# Snap2_audio.net
KiCad netlist of a schematic drawn in Altium Designer
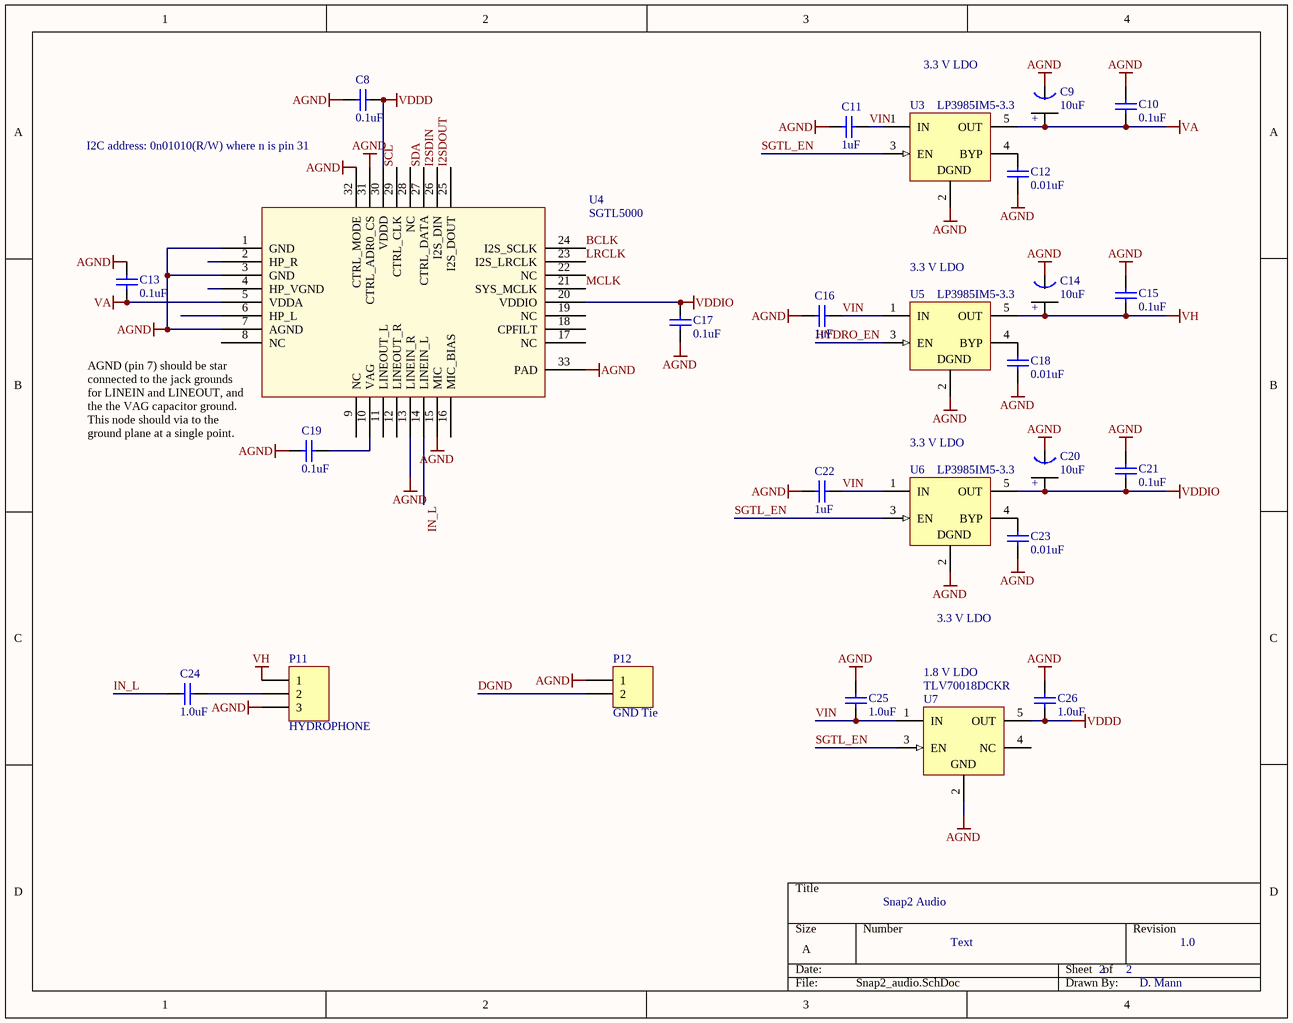
[diagram p0: Snap2_audio.SchDoc]

(export (version "E")
  (design (tool "Eeschema 10.0.6"))
  (components
    (comp (ref "C8")
      (value "0.1uF")
      (footprint "0402")
      (description "Ceramic Chip Capacitor - Standard")
      (fields (field (name "PUBLISHER") "Altium Limited"))
      (libsource (lib "KEMET Chip Capacitor") (part "C0402"))
    )
    (comp (ref "C9") (value "10uF") (footprint "Tant0805") (libsource (lib "Loggerhead") (part "Tant0805")))
    (comp (ref "C10")
      (value "0.1uF")
      (footprint "0402")
      (description "Ceramic Chip Capacitor - Standard")
      (fields (field (name "PUBLISHER") "Altium Limited"))
      (libsource (lib "KEMET Chip Capacitor") (part "C0402"))
    )
    (comp (ref "C11")
      (value "1uF")
      (footprint "0402")
      (description "Ceramic Chip Capacitor - Standard")
      (fields (field (name "PUBLISHER") "Altium Limited"))
      (libsource (lib "KEMET Chip Capacitor") (part "C0402"))
    )
    (comp (ref "C12")
      (value "0.01uF")
      (footprint "0402")
      (description "Ceramic Chip Capacitor - Standard")
      (fields (field (name "PUBLISHER") "Altium Limited"))
      (libsource (lib "KEMET Chip Capacitor") (part "C0402"))
    )
    (comp (ref "C13")
      (value "0.1uF")
      (footprint "0402")
      (description "Ceramic Chip Capacitor - Standard")
      (fields (field (name "PUBLISHER") "Altium Limited"))
      (libsource (lib "KEMET Chip Capacitor") (part "C0402"))
    )
    (comp (ref "C14") (value "10uF") (footprint "Tant0805") (libsource (lib "Loggerhead") (part "Tant0805")))
    (comp (ref "C15")
      (value "0.1uF")
      (footprint "0402")
      (description "Ceramic Chip Capacitor - Standard")
      (fields (field (name "PUBLISHER") "Altium Limited"))
      (libsource (lib "KEMET Chip Capacitor") (part "C0402"))
    )
    (comp (ref "C16")
      (value "1uF")
      (footprint "0402")
      (description "Ceramic Chip Capacitor - Standard")
      (fields (field (name "PUBLISHER") "Altium Limited"))
      (libsource (lib "KEMET Chip Capacitor") (part "C0402"))
    )
    (comp (ref "C17")
      (value "0.1uF")
      (footprint "0402")
      (description "Ceramic Chip Capacitor - Standard")
      (fields (field (name "PUBLISHER") "Altium Limited"))
      (libsource (lib "KEMET Chip Capacitor") (part "C0402"))
    )
    (comp (ref "C18")
      (value "0.01uF")
      (footprint "0402")
      (description "Ceramic Chip Capacitor - Standard")
      (fields (field (name "PUBLISHER") "Altium Limited"))
      (libsource (lib "KEMET Chip Capacitor") (part "C0402"))
    )
    (comp (ref "C19")
      (value "0.1uF")
      (footprint "0402")
      (description "Ceramic Chip Capacitor - Standard")
      (fields (field (name "PUBLISHER") "Altium Limited"))
      (libsource (lib "KEMET Chip Capacitor") (part "C0402"))
    )
    (comp (ref "C20") (value "10uF") (footprint "Tant0805") (libsource (lib "Loggerhead") (part "Tant0805")))
    (comp (ref "C21")
      (value "0.1uF")
      (footprint "0402")
      (description "Ceramic Chip Capacitor - Standard")
      (fields (field (name "PUBLISHER") "Altium Limited"))
      (libsource (lib "KEMET Chip Capacitor") (part "C0402"))
    )
    (comp (ref "C22")
      (value "1uF")
      (footprint "0402")
      (description "Ceramic Chip Capacitor - Standard")
      (fields (field (name "PUBLISHER") "Altium Limited"))
      (libsource (lib "KEMET Chip Capacitor") (part "C0402"))
    )
    (comp (ref "C23")
      (value "0.01uF")
      (footprint "0402")
      (description "Ceramic Chip Capacitor - Standard")
      (fields (field (name "PUBLISHER") "Altium Limited"))
      (libsource (lib "KEMET Chip Capacitor") (part "C0402"))
    )
    (comp (ref "C24")
      (value "1.0uF")
      (footprint "0402")
      (description "Ceramic Chip Capacitor - Standard")
      (fields (field (name "PUBLISHER") "Altium Limited"))
      (libsource (lib "KEMET Chip Capacitor") (part "C0402"))
    )
    (comp (ref "C25")
      (value "1.0uF")
      (footprint "0402")
      (description "Ceramic Chip Capacitor - Standard")
      (fields (field (name "PUBLISHER") "Altium Limited"))
      (libsource (lib "KEMET Chip Capacitor") (part "C0402"))
    )
    (comp (ref "C26")
      (value "1.0uF")
      (footprint "0402")
      (description "Ceramic Chip Capacitor - Standard")
      (fields (field (name "PUBLISHER") "Altium Limited"))
      (libsource (lib "KEMET Chip Capacitor") (part "C0402"))
    )
    (comp (ref "P11")
      (value "HYDROPHONE")
      (footprint "HDR1X3")
      (description "Header, 3-Pin")
      (fields (field (name "PUBLISHER") "Altium Limited"))
      (libsource (lib "Miscellaneous Connectors") (part "Header 3"))
    )
    (comp (ref "P12")
      (value "GND Tie")
      (footprint "HDR1X2")
      (description "Header, 2-Pin")
      (fields (field (name "PUBLISHER") "Altium Limited"))
      (libsource (lib "Miscellaneous Connectors") (part "Header 2"))
    )
    (comp (ref "U3")
      (value "LP3985IM5-3.3")
      (footprint "MF05A_N")
      (description "Micropower, 150mA Low-Noise Ultra Low-Dropout CMOS Voltage Regulator")
      (fields
        (field (name "MANUFACTURER") "National Semiconductor")
        (field (name "DIGIKEYPARTNUMBER") "LP3985IM5-3.3CT-ND")
        (field (name "PUBLISHER") "Altium Limited")
      )
      (libsource (lib "NSC LDO") (part "LP3985IM5-3.3"))
    )
    (comp (ref "U4") (value "SGTL5000") (footprint "QFN32") (libsource (lib "Loggerhead") (part "SGTL5000")))
    (comp (ref "U5")
      (value "LP3985IM5-3.3")
      (footprint "MF05A_N")
      (description "Micropower, 150mA Low-Noise Ultra Low-Dropout CMOS Voltage Regulator")
      (fields
        (field (name "MANUFACTURER") "National Semiconductor")
        (field (name "DIGIKEYPARTNUMBER") "LP3985IM5-3.3CT-ND")
        (field (name "PUBLISHER") "Altium Limited")
      )
      (libsource (lib "NSC LDO") (part "LP3985IM5-3.3"))
    )
    (comp (ref "U6")
      (value "LP3985IM5-3.3")
      (footprint "MF05A_N")
      (description "Micropower, 150mA Low-Noise Ultra Low-Dropout CMOS Voltage Regulator")
      (fields
        (field (name "MANUFACTURER") "National Semiconductor")
        (field (name "DIGIKEYPARTNUMBER") "LP3985IM5-3.3CT-ND")
        (field (name "PUBLISHER") "Altium Limited")
      )
      (libsource (lib "NSC LDO") (part "LP3985IM5-3.3"))
    )
    (comp (ref "U7")
      (value "TLV70018DCKR")
      (footprint "TI-DCK5_V")
      (fields (field (name "MANUFACTURER") "Texas Instruments"))
      (libsource (lib "TI Power Management Linear Regulator Single Channel LDO (0-350mA)") (part "TLV70018DCKR"))
    )
  )
  (nets
    (net (code "1") (name "/BCLK") (class "Default")
      (node (ref "U4") (pin "24") (pinfunction "I2S_SCLK_24") (pintype "passive"))
    )
    (net (code "2") (name "/DGND") (class "Default")
      (node (ref "P12") (pin "2") (pinfunction "2_2") (pintype "passive"))
    )
    (net (code "3") (name "/HYDRO_EN") (class "Default")
      (node (ref "U5") (pin "3") (pinfunction "EN_3") (pintype "input"))
    )
    (net (code "4") (name "/I2SDIN") (class "Default")
      (node (ref "U4") (pin "26") (pinfunction "I2S_DIN_26") (pintype "passive"))
    )
    (net (code "5") (name "/I2SDOUT") (class "Default")
      (node (ref "U4") (pin "25") (pinfunction "I2S_DOUT_25") (pintype "passive"))
    )
    (net (code "6") (name "/IN_L") (class "Default")
      (node (ref "C24") (pin "2") (pinfunction "2_2") (pintype "passive"))
      (node (ref "U4") (pin "14") (pinfunction "LINEIN_L_14") (pintype "passive"))
    )
    (net (code "7") (name "/LRCLK") (class "Default")
      (node (ref "U4") (pin "23") (pinfunction "I2S_LRCLK_23") (pintype "passive"))
    )
    (net (code "8") (name "/MCLK") (class "Default")
      (node (ref "U4") (pin "21") (pinfunction "SYS_MCLK_21") (pintype "passive"))
    )
    (net (code "9") (name "/SCL") (class "Default")
      (node (ref "U4") (pin "29") (pinfunction "CTRL_CLK_29") (pintype "passive"))
    )
    (net (code "10") (name "/SDA") (class "Default")
      (node (ref "U4") (pin "27") (pinfunction "CTRL_DATA_27") (pintype "passive"))
    )
    (net (code "11") (name "/SGTL_EN") (class "Default")
      (node (ref "U3") (pin "3") (pinfunction "EN_3") (pintype "input"))
      (node (ref "U6") (pin "3") (pinfunction "EN_3") (pintype "input"))
      (node (ref "U7") (pin "3") (pinfunction "EN_3") (pintype "input"))
    )
    (net (code "12") (name "/VIN") (class "Default")
      (node (ref "C11") (pin "1") (pinfunction "1_1") (pintype "passive"))
      (node (ref "C16") (pin "1") (pinfunction "1_1") (pintype "passive"))
      (node (ref "C22") (pin "1") (pinfunction "1_1") (pintype "passive"))
      (node (ref "C25") (pin "1") (pinfunction "1_1") (pintype "passive"))
      (node (ref "U3") (pin "1") (pinfunction "IN_1") (pintype "power_in"))
      (node (ref "U5") (pin "1") (pinfunction "IN_1") (pintype "power_in"))
      (node (ref "U6") (pin "1") (pinfunction "IN_1") (pintype "power_in"))
      (node (ref "U7") (pin "1") (pinfunction "IN_1") (pintype "power_in"))
    )
    (net (code "13") (name "AGND") (class "Default")
      (node (ref "C10") (pin "2") (pinfunction "2_2") (pintype "passive"))
      (node (ref "C11") (pin "2") (pinfunction "2_2") (pintype "passive"))
      (node (ref "C12") (pin "2") (pinfunction "2_2") (pintype "passive"))
      (node (ref "C13") (pin "2") (pinfunction "2_2") (pintype "passive"))
      (node (ref "C14") (pin "1") (pinfunction "GND_1") (pintype "passive"))
      (node (ref "C15") (pin "2") (pinfunction "2_2") (pintype "passive"))
      (node (ref "C16") (pin "2") (pinfunction "2_2") (pintype "passive"))
      (node (ref "C17") (pin "2") (pinfunction "2_2") (pintype "passive"))
      (node (ref "C18") (pin "2") (pinfunction "2_2") (pintype "passive"))
      (node (ref "C19") (pin "2") (pinfunction "2_2") (pintype "passive"))
      (node (ref "C20") (pin "1") (pinfunction "GND_1") (pintype "passive"))
      (node (ref "C21") (pin "2") (pinfunction "2_2") (pintype "passive"))
      (node (ref "C22") (pin "2") (pinfunction "2_2") (pintype "passive"))
      (node (ref "C23") (pin "2") (pinfunction "2_2") (pintype "passive"))
      (node (ref "C25") (pin "2") (pinfunction "2_2") (pintype "passive"))
      (node (ref "C26") (pin "2") (pinfunction "2_2") (pintype "passive"))
      (node (ref "C8") (pin "2") (pinfunction "2_2") (pintype "passive"))
      (node (ref "C9") (pin "1") (pinfunction "GND_1") (pintype "passive"))
      (node (ref "P11") (pin "3") (pinfunction "3_3") (pintype "passive"))
      (node (ref "P12") (pin "1") (pinfunction "1_1") (pintype "passive"))
      (node (ref "U3") (pin "2") (pinfunction "GND_2") (pintype "power_in"))
      (node (ref "U4") (pin "1") (pinfunction "GND_1") (pintype "passive"))
      (node (ref "U4") (pin "13") (pinfunction "LINEIN_R_13") (pintype "passive"))
      (node (ref "U4") (pin "15") (pinfunction "MIC_15") (pintype "passive"))
      (node (ref "U4") (pin "3") (pinfunction "GND_3") (pintype "passive"))
      (node (ref "U4") (pin "31") (pinfunction "CTRL_ADR0_CS_31") (pintype "passive"))
      (node (ref "U4") (pin "32") (pinfunction "CTRL_MODE_32") (pintype "passive"))
      (node (ref "U4") (pin "33") (pinfunction "PAD_33") (pintype "passive"))
      (node (ref "U4") (pin "7") (pinfunction "AGND_7") (pintype "passive"))
      (node (ref "U5") (pin "2") (pinfunction "GND_2") (pintype "power_in"))
      (node (ref "U6") (pin "2") (pinfunction "GND_2") (pintype "power_in"))
      (node (ref "U7") (pin "2") (pinfunction "GND_2") (pintype "power_in"))
    )
    (net (code "14") (name "Net-(C24-Pad1)") (class "Default")
      (node (ref "C24") (pin "1") (pinfunction "1_1") (pintype "passive"))
      (node (ref "P11") (pin "2") (pinfunction "2_2") (pintype "passive"))
    )
    (net (code "15") (name "Net-(U3-BYP)") (class "Default")
      (node (ref "C12") (pin "1") (pinfunction "1_1") (pintype "passive"))
      (node (ref "U3") (pin "4") (pinfunction "BYP_4") (pintype "passive"))
    )
    (net (code "16") (name "Net-(U4-VAG)") (class "Default")
      (node (ref "C19") (pin "1") (pinfunction "1_1") (pintype "passive"))
      (node (ref "U4") (pin "10") (pinfunction "VAG_10") (pintype "passive"))
    )
    (net (code "17") (name "Net-(U5-BYP)") (class "Default")
      (node (ref "C18") (pin "1") (pinfunction "1_1") (pintype "passive"))
      (node (ref "U5") (pin "4") (pinfunction "BYP_4") (pintype "passive"))
    )
    (net (code "18") (name "Net-(U6-BYP)") (class "Default")
      (node (ref "C23") (pin "1") (pinfunction "1_1") (pintype "passive"))
      (node (ref "U6") (pin "4") (pinfunction "BYP_4") (pintype "passive"))
    )
    (net (code "19") (name "VA") (class "Default")
      (node (ref "C10") (pin "1") (pinfunction "1_1") (pintype "passive"))
      (node (ref "C13") (pin "1") (pinfunction "1_1") (pintype "passive"))
      (node (ref "C9") (pin "2") (pinfunction "+_2") (pintype "passive"))
      (node (ref "U3") (pin "5") (pinfunction "OUT_5") (pintype "power_in"))
      (node (ref "U4") (pin "5") (pinfunction "VDDA_5") (pintype "passive"))
    )
    (net (code "20") (name "VDDD") (class "Default")
      (node (ref "C26") (pin "1") (pinfunction "1_1") (pintype "passive"))
      (node (ref "C8") (pin "1") (pinfunction "1_1") (pintype "passive"))
      (node (ref "U4") (pin "30") (pinfunction "VDDD_30") (pintype "passive"))
      (node (ref "U7") (pin "5") (pinfunction "OUT_5") (pintype "power_in"))
    )
    (net (code "21") (name "VDDIO") (class "Default")
      (node (ref "C17") (pin "1") (pinfunction "1_1") (pintype "passive"))
      (node (ref "C20") (pin "2") (pinfunction "+_2") (pintype "passive"))
      (node (ref "C21") (pin "1") (pinfunction "1_1") (pintype "passive"))
      (node (ref "U4") (pin "20") (pinfunction "VDDIO_20") (pintype "passive"))
      (node (ref "U6") (pin "5") (pinfunction "OUT_5") (pintype "power_in"))
    )
    (net (code "22") (name "VH") (class "Default")
      (node (ref "C14") (pin "2") (pinfunction "+_2") (pintype "passive"))
      (node (ref "C15") (pin "1") (pinfunction "1_1") (pintype "passive"))
      (node (ref "P11") (pin "1") (pinfunction "1_1") (pintype "passive"))
      (node (ref "U5") (pin "5") (pinfunction "OUT_5") (pintype "power_in"))
    )
    (net (code "23") (name "unconnected-(U4-CPFILT-Pad18)") (class "Default")
      (node (ref "U4") (pin "18") (pinfunction "CPFILT_18") (pintype "passive"))
    )
    (net (code "24") (name "unconnected-(U4-HP_L-Pad6)") (class "Default")
      (node (ref "U4") (pin "6") (pinfunction "HP_L_6") (pintype "passive"))
    )
    (net (code "25") (name "unconnected-(U4-HP_R-Pad2)") (class "Default")
      (node (ref "U4") (pin "2") (pinfunction "HP_R_2") (pintype "passive"))
    )
    (net (code "26") (name "unconnected-(U4-HP_VGND-Pad4)") (class "Default")
      (node (ref "U4") (pin "4") (pinfunction "HP_VGND_4") (pintype "passive"))
    )
    (net (code "27") (name "unconnected-(U4-LINEOUT_L-Pad11)") (class "Default")
      (node (ref "U4") (pin "11") (pinfunction "LINEOUT_L_11") (pintype "passive"))
    )
    (net (code "28") (name "unconnected-(U4-LINEOUT_R-Pad12)") (class "Default")
      (node (ref "U4") (pin "12") (pinfunction "LINEOUT_R_12") (pintype "passive"))
    )
    (net (code "29") (name "unconnected-(U4-MIC_BIAS-Pad16)") (class "Default")
      (node (ref "U4") (pin "16") (pinfunction "MIC_BIAS_16") (pintype "passive"))
    )
    (net (code "30") (name "unconnected-(U4-NC-Pad8)") (class "Default")
      (node (ref "U4") (pin "8") (pinfunction "NC_8") (pintype "passive"))
    )
    (net (code "31") (name "unconnected-(U4-NC-Pad9)") (class "Default")
      (node (ref "U4") (pin "9") (pinfunction "NC_9") (pintype "passive"))
    )
    (net (code "32") (name "unconnected-(U4-NC-Pad17)") (class "Default")
      (node (ref "U4") (pin "17") (pinfunction "NC_17") (pintype "passive"))
    )
    (net (code "33") (name "unconnected-(U4-NC-Pad19)") (class "Default")
      (node (ref "U4") (pin "19") (pinfunction "NC_19") (pintype "passive"))
    )
    (net (code "34") (name "unconnected-(U4-NC-Pad22)") (class "Default")
      (node (ref "U4") (pin "22") (pinfunction "NC_22") (pintype "passive"))
    )
    (net (code "35") (name "unconnected-(U4-NC-Pad28)") (class "Default")
      (node (ref "U4") (pin "28") (pinfunction "NC_28") (pintype "passive"))
    )
    (net (code "36") (name "unconnected-(U7-NC-Pad4)") (class "Default")
      (node (ref "U7") (pin "4") (pinfunction "NC_4") (pintype "passive"))
    )
  )
)
